# tritiled_v31_oslon.net
KiCad netlist of a schematic drawn in EAGLE
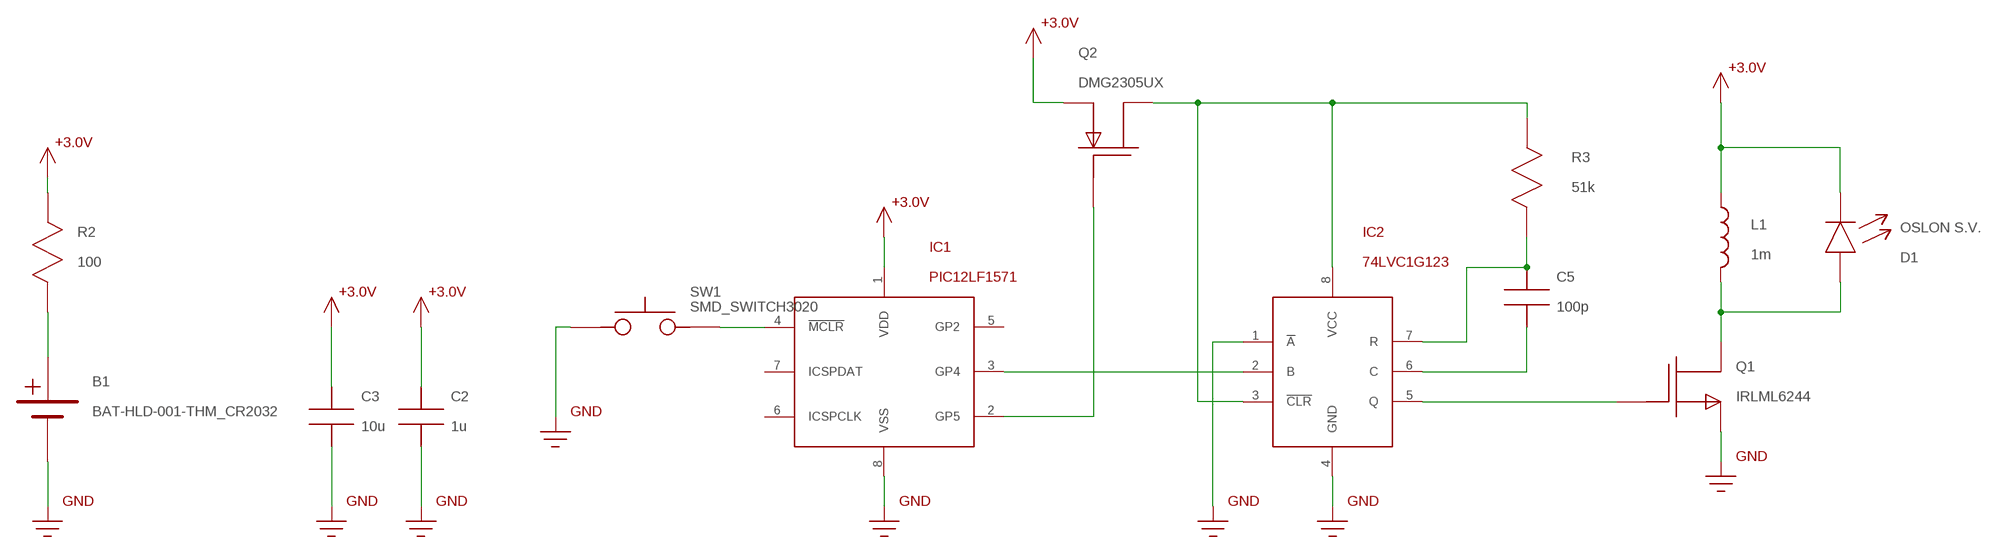
[diagram p0: schematic, sheet 1]

(export (version "E")
  (design (tool "Eeschema 10.0.6"))
  (components
    (comp (ref "B1")
      (value "BAT-HLD-001-THM_CR2032")
      (footprint "eagle-import:CR2032_BAT-HLD-001-THM")
      (libsource (lib "eagle-import") (part "BAT-HLD-001-THM_CR2032"))
    )
    (comp (ref "C2")
      (value "1u")
      (footprint "eagle-import:0805")
      (libsource (lib "eagle-import") (part "C0805"))
    )
    (comp (ref "C3")
      (value "10u")
      (footprint "eagle-import:1206")
      (libsource (lib "eagle-import") (part "C1206"))
    )
    (comp (ref "C5")
      (value "100p")
      (footprint "eagle-import:C0603")
      (libsource (lib "eagle-import") (part "C0603"))
    )
    (comp (ref "D1")
      (value "OSLON S.V.")
      (footprint "eagle-import:OSLON_3030_LED")
      (libsource (lib "eagle-import") (part "OSLON_SIGNAL"))
    )
    (comp (ref "IC1")
      (value "PIC12LF1571")
      (footprint "eagle-import:SOIC8")
      (libsource (lib "eagle-import") (part "PIC12LF1571"))
    )
    (comp (ref "IC2")
      (value "74LVC1G123")
      (footprint "eagle-import:SM8")
      (libsource (lib "eagle-import") (part "74LVC1G123"))
    )
    (comp (ref "L1")
      (value "1m")
      (footprint "eagle-import:SRR6028_INDUCTOR")
      (libsource (lib "eagle-import") (part "SRR6028_INDUCTOR"))
    )
    (comp (ref "Q1")
      (value "IRLML6244")
      (footprint "eagle-import:SOT-23")
      (libsource (lib "eagle-import") (part "ZXMN3B01FSOT23"))
    )
    (comp (ref "Q2")
      (value "DMG2305UX")
      (footprint "eagle-import:SOT-23")
      (libsource (lib "eagle-import") (part "DMG2305UXSOT23"))
    )
    (comp (ref "R2")
      (value "100")
      (footprint "eagle-import:R1206")
      (libsource (lib "eagle-import") (part "R1206"))
    )
    (comp (ref "R3")
      (value "51k")
      (footprint "eagle-import:R0603")
      (libsource (lib "eagle-import") (part "R0603"))
    )
    (comp (ref "SW1")
      (value "SMD_SWITCH3020")
      (footprint "eagle-import:SWITCH_3020")
      (libsource (lib "eagle-import") (part "SMD_SWITCH3020"))
    )
  )
  (nets
    (net (code "1") (name "+3.0V") (class "Default")
      (node (ref "C2") (pin "P$1") (pinfunction "P$1_P$1") (pintype "bidirectional"))
      (node (ref "C3") (pin "P$1") (pinfunction "P$1_P$1") (pintype "bidirectional"))
      (node (ref "D1") (pin "C") (pinfunction "C_C") (pintype "bidirectional"))
      (node (ref "IC1") (pin "1") (pinfunction "VDD_1") (pintype "bidirectional"))
      (node (ref "L1") (pin "P$1") (pinfunction "1_P$1") (pintype "passive"))
      (node (ref "Q2") (pin "2") (pinfunction "S_2") (pintype "bidirectional"))
      (node (ref "R2") (pin "P$1") (pinfunction "P$1_P$1") (pintype "bidirectional"))
    )
    (net (code "2") (name "GND") (class "Default")
      (node (ref "B1") (pin "GND") (pinfunction "0V_GND") (pintype "power_in"))
      (node (ref "C2") (pin "P$2") (pinfunction "P$2_P$2") (pintype "bidirectional"))
      (node (ref "C3") (pin "P$2") (pinfunction "P$2_P$2") (pintype "bidirectional"))
      (node (ref "IC1") (pin "8") (pinfunction "VSS_8") (pintype "bidirectional"))
      (node (ref "IC2") (pin "1") (pinfunction "~{A}_1") (pintype "bidirectional"))
      (node (ref "IC2") (pin "4") (pinfunction "GND_4") (pintype "bidirectional"))
      (node (ref "Q1") (pin "2") (pinfunction "S_2") (pintype "bidirectional"))
      (node (ref "SW1") (pin "A") (pinfunction "P$1_A") (pintype "bidirectional"))
    )
    (net (code "3") (name "Net-(B1-+V-Pad+V@1)") (class "Default")
      (node (ref "B1") (pin "+V@1") (pinfunction "+V_+V@1") (pintype "power_in"))
      (node (ref "B1") (pin "+V@2") (pinfunction "+V_+V@2") (pintype "power_in"))
      (node (ref "B1") (pin "+V@3") (pinfunction "+V_+V@3") (pintype "power_in"))
      (node (ref "B1") (pin "+V@4") (pinfunction "+V_+V@4") (pintype "power_in"))
      (node (ref "R2") (pin "P$2") (pinfunction "P$2_P$2") (pintype "bidirectional"))
    )
    (net (code "4") (name "Net-(IC1-GP4)") (class "Default")
      (node (ref "IC1") (pin "3") (pinfunction "GP4_3") (pintype "bidirectional"))
      (node (ref "IC2") (pin "2") (pinfunction "B_2") (pintype "bidirectional"))
    )
    (net (code "5") (name "Net-(IC1-GP5)") (class "Default")
      (node (ref "IC1") (pin "2") (pinfunction "GP5_2") (pintype "bidirectional"))
      (node (ref "Q2") (pin "1") (pinfunction "G_1") (pintype "bidirectional"))
    )
    (net (code "6") (name "Net-(IC1-~{MCLR})") (class "Default")
      (node (ref "IC1") (pin "4") (pinfunction "~{MCLR}_4") (pintype "bidirectional"))
      (node (ref "SW1") (pin "B") (pinfunction "P$2_B") (pintype "bidirectional"))
    )
    (net (code "7") (name "Net-(IC2-C)") (class "Default")
      (node (ref "C5") (pin "P$2") (pinfunction "P$2_P$2") (pintype "bidirectional"))
      (node (ref "IC2") (pin "6") (pinfunction "C_6") (pintype "bidirectional"))
    )
    (net (code "8") (name "Net-(IC2-Q)") (class "Default")
      (node (ref "IC2") (pin "5") (pinfunction "Q_5") (pintype "bidirectional"))
      (node (ref "Q1") (pin "1") (pinfunction "G_1") (pintype "bidirectional"))
    )
    (net (code "9") (name "Net-(IC2-R)") (class "Default")
      (node (ref "C5") (pin "P$1") (pinfunction "P$1_P$1") (pintype "bidirectional"))
      (node (ref "IC2") (pin "7") (pinfunction "R_7") (pintype "bidirectional"))
      (node (ref "R3") (pin "P$1") (pinfunction "P$1_P$1") (pintype "bidirectional"))
    )
    (net (code "10") (name "Net-(IC2-VCC)") (class "Default")
      (node (ref "IC2") (pin "3") (pinfunction "~{CLR}_3") (pintype "bidirectional"))
      (node (ref "IC2") (pin "8") (pinfunction "VCC_8") (pintype "bidirectional"))
      (node (ref "Q2") (pin "3") (pinfunction "D_3") (pintype "bidirectional"))
      (node (ref "R3") (pin "P$2") (pinfunction "P$2_P$2") (pintype "bidirectional"))
    )
    (net (code "11") (name "Net-(L1-2)") (class "Default")
      (node (ref "D1") (pin "A") (pinfunction "A_A") (pintype "bidirectional"))
      (node (ref "L1") (pin "P$2") (pinfunction "2_P$2") (pintype "passive"))
      (node (ref "Q1") (pin "3") (pinfunction "D_3") (pintype "bidirectional"))
    )
    (net (code "12") (name "unconnected-(IC1-GP2-Pad5)") (class "Default")
      (node (ref "IC1") (pin "5") (pinfunction "GP2_5") (pintype "bidirectional"))
    )
    (net (code "13") (name "unconnected-(IC1-ICSPCLK-Pad6)") (class "Default")
      (node (ref "IC1") (pin "6") (pinfunction "ICSPCLK_6") (pintype "bidirectional"))
    )
    (net (code "14") (name "unconnected-(IC1-ICSPDAT-Pad7)") (class "Default")
      (node (ref "IC1") (pin "7") (pinfunction "ICSPDAT_7") (pintype "bidirectional"))
    )
  )
)
